# VUSB_BREAKOUT_V1.net
KiCad netlist of a schematic drawn in EAGLE
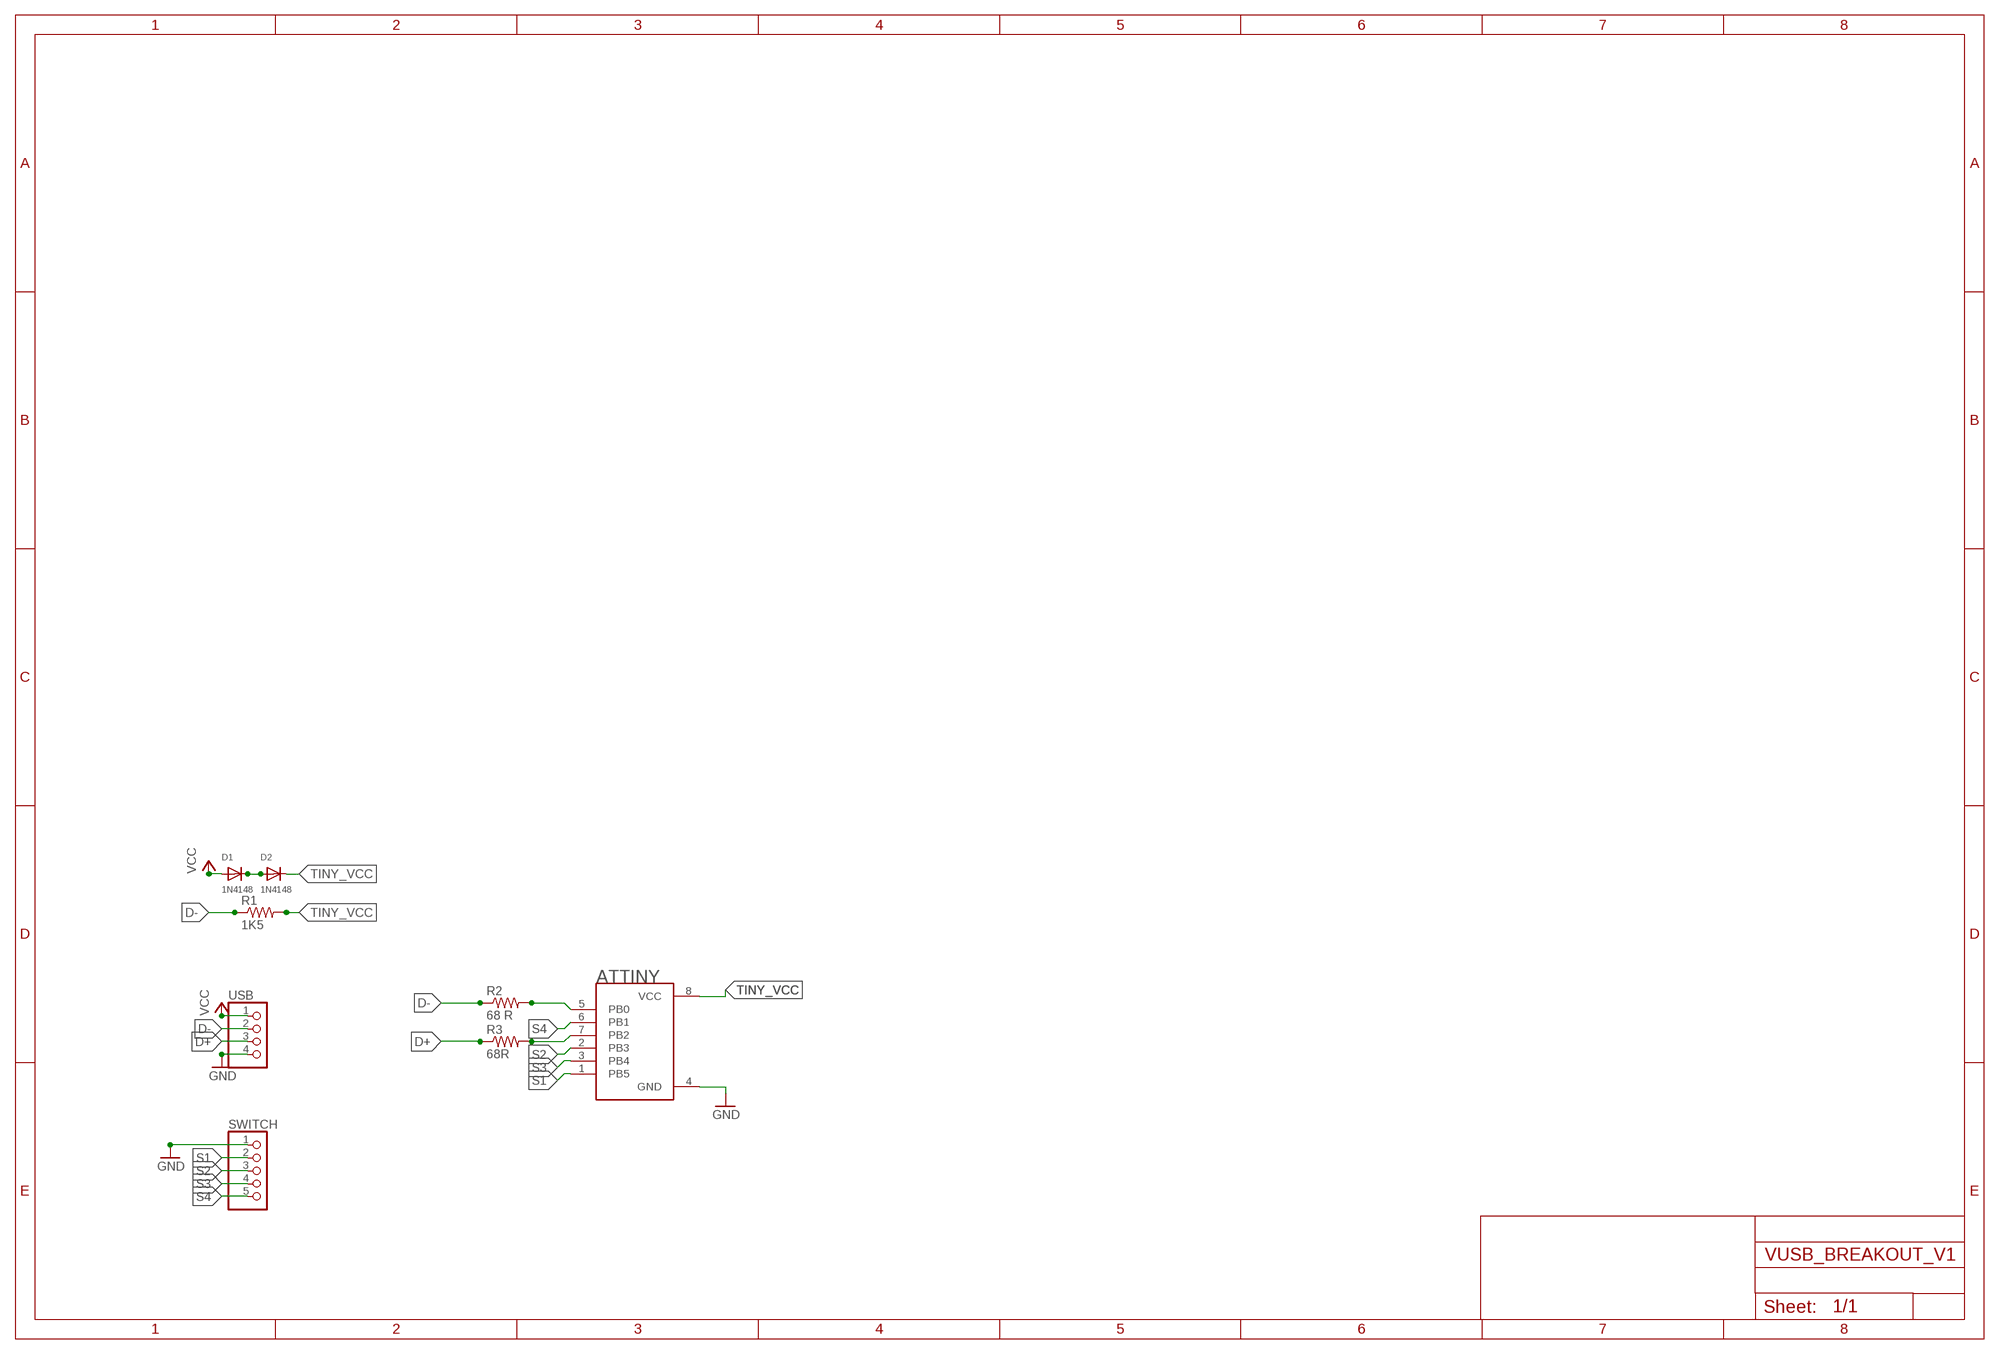
[diagram p0: schematic, sheet 1]

(export (version "E")
  (design (tool "Eeschema 10.0.6"))
  (components
    (comp (ref "ATTINY")
      (value "ATTINY85-20PU")
      (footprint "eagle-import:DIP762W46P254L927H533Q8B")
      (fields (field (name "MF") "Microchip"))
      (libsource (lib "eagle-import") (part "ATTINY85-20PU"))
    )
    (comp (ref "D1")
      (value "1N4148")
      (footprint "eagle-import:DO-1N4148")
      (libsource (lib "eagle-import") (part "DIODEDO-1N4148"))
    )
    (comp (ref "D2")
      (value "1N4148")
      (footprint "eagle-import:DO-1N4148")
      (libsource (lib "eagle-import") (part "DIODEDO-1N4148"))
    )
    (comp (ref "R1")
      (value "1K5")
      (footprint "eagle-import:0207_15")
      (libsource (lib "eagle-import") (part "R-US_0207/15"))
    )
    (comp (ref "R2")
      (value "68 R")
      (footprint "eagle-import:0207_15")
      (libsource (lib "eagle-import") (part "R-US_0207/15"))
    )
    (comp (ref "R3")
      (value "68R")
      (footprint "eagle-import:0207_15")
      (libsource (lib "eagle-import") (part "R-US_0207/15"))
    )
    (comp (ref "SWITCH")
      (value "PINHD-1X5")
      (footprint "eagle-import:1X05")
      (libsource (lib "eagle-import") (part "PINHD-1X5"))
    )
    (comp (ref "USB")
      (value "PINHD-1X4")
      (footprint "eagle-import:1X04")
      (libsource (lib "eagle-import") (part "PINHD-1X4"))
    )
  )
  (nets
    (net (code "1") (name "D+") (class "Default")
      (node (ref "R3") (pin "1") (pinfunction "1_1") (pintype "passive"))
      (node (ref "USB") (pin "3") (pinfunction "3_3") (pintype "passive"))
    )
    (net (code "2") (name "D-") (class "Default")
      (node (ref "R1") (pin "1") (pinfunction "1_1") (pintype "passive"))
      (node (ref "R2") (pin "1") (pinfunction "1_1") (pintype "passive"))
      (node (ref "USB") (pin "2") (pinfunction "2_2") (pintype "passive"))
    )
    (net (code "3") (name "GND") (class "Default")
      (node (ref "ATTINY") (pin "4") (pinfunction "GND_4") (pintype "power_in"))
      (node (ref "SWITCH") (pin "1") (pinfunction "1_1") (pintype "passive"))
      (node (ref "USB") (pin "4") (pinfunction "4_4") (pintype "passive"))
    )
    (net (code "4") (name "Net-(ATTINY-PB0)") (class "Default")
      (node (ref "ATTINY") (pin "5") (pinfunction "PB0_5") (pintype "bidirectional"))
      (node (ref "R2") (pin "2") (pinfunction "2_2") (pintype "passive"))
    )
    (net (code "5") (name "Net-(ATTINY-PB2)") (class "Default")
      (node (ref "ATTINY") (pin "7") (pinfunction "PB2_7") (pintype "bidirectional"))
      (node (ref "R3") (pin "2") (pinfunction "2_2") (pintype "passive"))
    )
    (net (code "6") (name "Net-(D1-PadC)") (class "Default")
      (node (ref "D1") (pin "C") (pinfunction "C_C") (pintype "passive"))
      (node (ref "D2") (pin "A") (pinfunction "A_A") (pintype "passive"))
    )
    (net (code "7") (name "S1") (class "Default")
      (node (ref "ATTINY") (pin "1") (pinfunction "PB5_1") (pintype "bidirectional"))
      (node (ref "SWITCH") (pin "2") (pinfunction "2_2") (pintype "passive"))
    )
    (net (code "8") (name "S2") (class "Default")
      (node (ref "ATTINY") (pin "2") (pinfunction "PB3_2") (pintype "bidirectional"))
      (node (ref "SWITCH") (pin "3") (pinfunction "3_3") (pintype "passive"))
    )
    (net (code "9") (name "S3") (class "Default")
      (node (ref "ATTINY") (pin "3") (pinfunction "PB4_3") (pintype "bidirectional"))
      (node (ref "SWITCH") (pin "4") (pinfunction "4_4") (pintype "passive"))
    )
    (net (code "10") (name "S4") (class "Default")
      (node (ref "ATTINY") (pin "6") (pinfunction "PB1_6") (pintype "bidirectional"))
      (node (ref "SWITCH") (pin "5") (pinfunction "5_5") (pintype "passive"))
    )
    (net (code "11") (name "TINY_VCC") (class "Default")
      (node (ref "ATTINY") (pin "8") (pinfunction "VCC_8") (pintype "power_in"))
      (node (ref "D2") (pin "C") (pinfunction "C_C") (pintype "passive"))
      (node (ref "R1") (pin "2") (pinfunction "2_2") (pintype "passive"))
    )
    (net (code "12") (name "VCC") (class "Default")
      (node (ref "D1") (pin "A") (pinfunction "A_A") (pintype "passive"))
      (node (ref "USB") (pin "1") (pinfunction "1_1") (pintype "passive"))
    )
  )
)
